# Power.net
KiCad netlist of a schematic drawn in Altium Designer
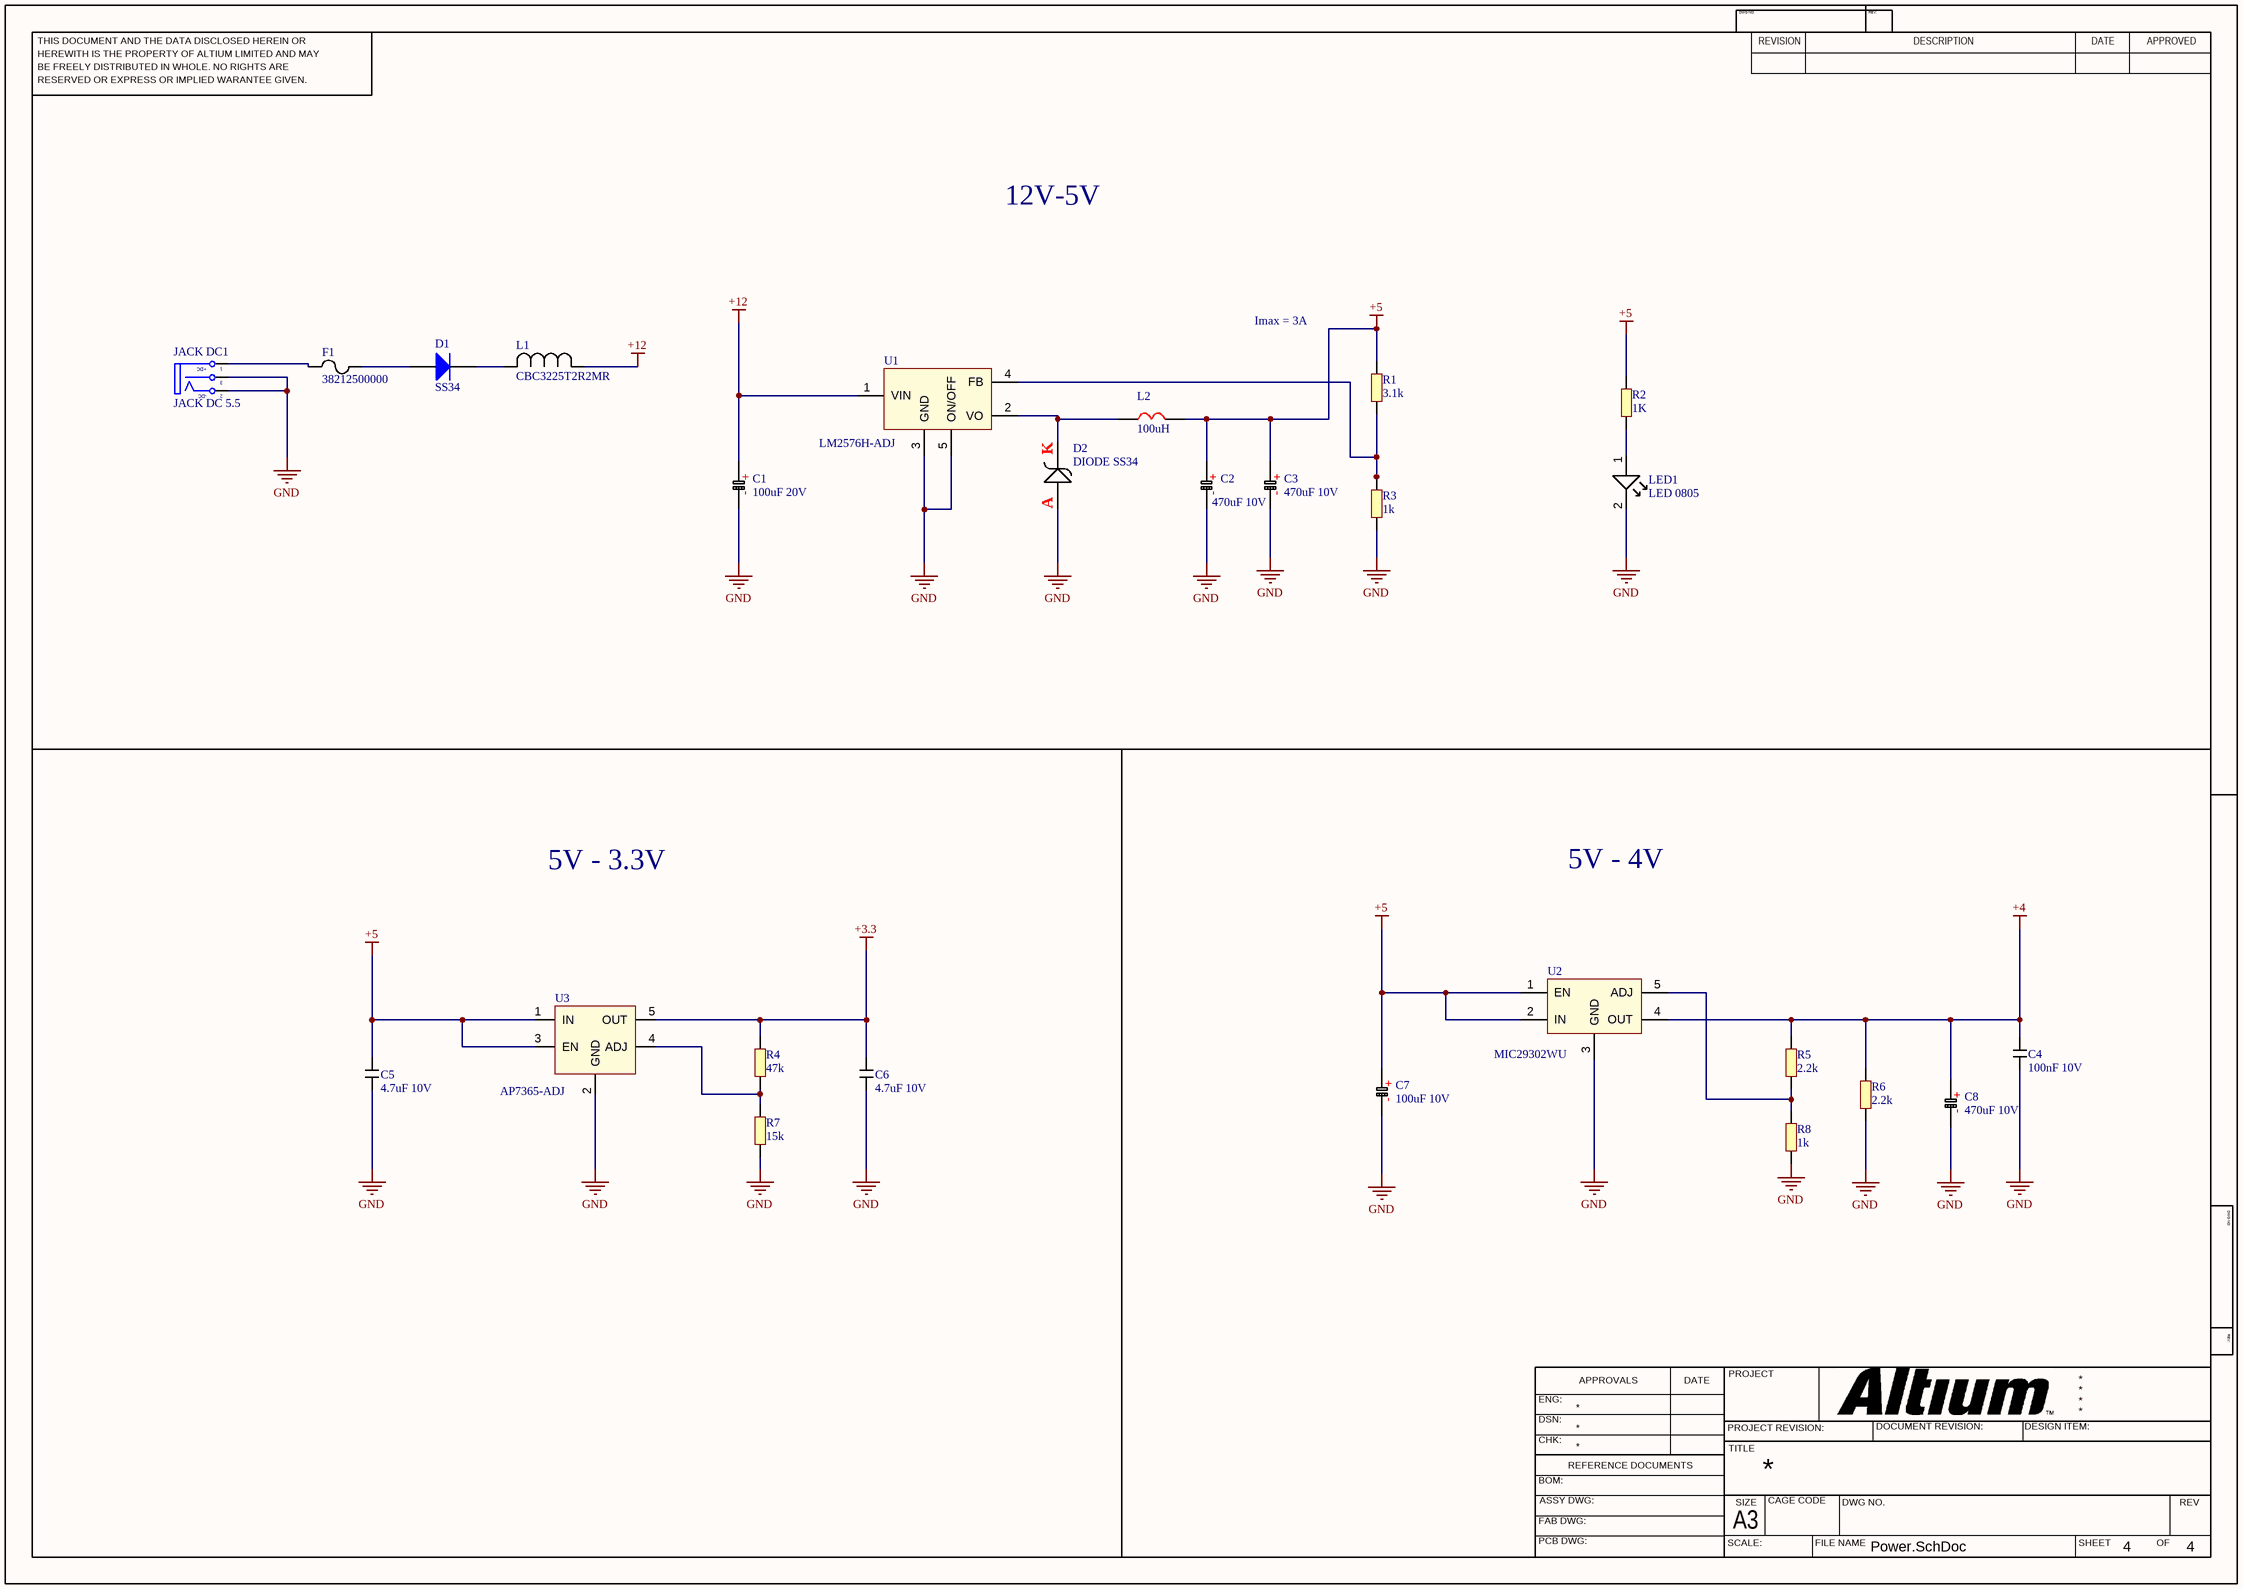
[diagram p0: Power.SchDoc]

(export (version "E")
  (design (tool "Eeschema 10.0.6"))
  (components
    (comp (ref "C1")
      (value "100uF 20V")
      (footprint "CAPACITOR TALTALIUM 7443")
      (libsource (lib "NAVISTAR") (part "C Polarize 8x10.2"))
    )
    (comp (ref "C2")
      (value "470uF 10V")
      (footprint "CAPACITOR TALTALIUM 7443")
      (libsource (lib "NAVISTAR") (part "C Polarize 8x10.2"))
    )
    (comp (ref "C3")
      (value "470uF 10V")
      (footprint "CAPACITOR TALTALIUM 7443")
      (libsource (lib "NAVISTAR") (part "C Polarize 8x10.2"))
    )
    (comp (ref "C4") (value "100nF 10V") (footprint "c 0805") (libsource (lib "NAVISTAR") (part "C 0805")))
    (comp (ref "C5") (value "4.7uF 10V") (footprint "c 0805") (libsource (lib "NAVISTAR") (part "C 0805")))
    (comp (ref "C6") (value "4.7uF 10V") (footprint "c 0805") (libsource (lib "NAVISTAR") (part "C 0805")))
    (comp (ref "C7")
      (value "100uF 10V")
      (footprint "CAPACITOR TALTALIUM 7443")
      (libsource (lib "NAVISTAR") (part "C Polarize 8x10.2"))
    )
    (comp (ref "C8")
      (value "470uF 10V")
      (footprint "CAPACITOR TALTALIUM 7443")
      (libsource (lib "NAVISTAR") (part "C Polarize 8x10.2"))
    )
    (comp (ref "D1")
      (value "SS34")
      (footprint "DIODE SMA")
      (description "Dán")
      (libsource (lib "Altium_Lib_by_KhueNguyenCreator") (part "Diode SS34 ( 1N5822 )"))
    )
    (comp (ref "D2")
      (value "DIODE SS34")
      (footprint "DIODE SS34")
      (libsource (lib "NAVISTAR") (part "DIODE SS34"))
    )
    (comp (ref "F1")
      (value "38212500000")
      (footprint "FUSE_38212500000_LTF")
      (description "No Description Available")
      (fields (field (name "COPYRIGHT") "Copyright (C) 2023 Ultra Librarian. All rights reserved."))
      (libsource (lib "FUSE_38212500000_LTF") (part "38212500000"))
    )
    (comp (ref "JACK DC1")
      (value "JACK DC 5.5")
      (footprint "JACK DC 5.5")
      (libsource (lib "Altium_Lib_by_KhueNguyenCreator") (part "JACK DC 5.5"))
    )
    (comp (ref "L1")
      (value "CBC3225T2R2MR")
      (footprint "IND_TAIYO_CBC3225_TAY")
      (description "No Description Available")
      (fields (field (name "COPYRIGHT") "Copyright (C) 2023 Ultra Librarian. All rights reserved."))
      (libsource (lib "CBC3225T2R2MR") (part "CBC3225T2R2MR"))
    )
    (comp (ref "L2") (value "100uH") (footprint "L 4600") (libsource (lib "NAVISTAR") (part "L 4600")))
    (comp (ref "LED1")
      (value "LED 0805")
      (footprint "LED 0805")
      (libsource (lib "NAVISTAR") (part "LED 0805"))
    )
    (comp (ref "R1") (value "3.1k") (footprint "R 0805") (libsource (lib "NAVISTAR") (part "R 0805")))
    (comp (ref "R2") (value "1K") (footprint "R 0805") (libsource (lib "NAVISTAR") (part "R 0805")))
    (comp (ref "R3") (value "1k") (footprint "R 0805") (libsource (lib "NAVISTAR") (part "R 0805")))
    (comp (ref "R4") (value "47k") (footprint "R 0805") (libsource (lib "NAVISTAR") (part "R 0805")))
    (comp (ref "R5") (value "2.2k") (footprint "R 0805") (libsource (lib "NAVISTAR") (part "R 0805")))
    (comp (ref "R6") (value "2.2k") (footprint "R 0805") (libsource (lib "NAVISTAR") (part "R 0805")))
    (comp (ref "R7") (value "15k") (footprint "R 0805") (libsource (lib "NAVISTAR") (part "R 0805")))
    (comp (ref "R8") (value "1k") (footprint "R 0805") (libsource (lib "NAVISTAR") (part "R 0805")))
    (comp (ref "U1")
      (value "LM2576H-ADJ")
      (footprint "LM2576H")
      (libsource (lib "NAVISTAR") (part "LM2576H"))
    )
    (comp (ref "U2")
      (value "MIC29302WU")
      (footprint "MIC29302WU")
      (libsource (lib "NAVISTAR_SoC") (part "MIC29302WU"))
    )
    (comp (ref "U3")
      (value "AP7365-ADJ")
      (footprint "AP7365-ADJ")
      (libsource (lib "NAVISTAR") (part "AP7365-ADJ"))
    )
  )
  (nets
    (net (code "1") (name "+3.3") (class "Default")
      (node (ref "C6") (pin "2") (pintype "passive"))
      (node (ref "R4") (pin "2") (pintype "passive"))
      (node (ref "U3") (pin "5") (pinfunction "OUT_5") (pintype "passive"))
    )
    (net (code "2") (name "+4") (class "Default")
      (node (ref "C4") (pin "2") (pintype "passive"))
      (node (ref "C8") (pin "1") (pintype "passive"))
      (node (ref "R5") (pin "2") (pintype "passive"))
      (node (ref "R6") (pin "2") (pintype "passive"))
      (node (ref "U2") (pin "4") (pinfunction "OUT_4") (pintype "passive"))
    )
    (net (code "3") (name "+5") (class "Default")
      (node (ref "C2") (pin "1") (pintype "passive"))
      (node (ref "C3") (pin "1") (pintype "passive"))
      (node (ref "C5") (pin "2") (pintype "passive"))
      (node (ref "C7") (pin "1") (pintype "passive"))
      (node (ref "L2") (pin "2") (pintype "passive"))
      (node (ref "R1") (pin "2") (pintype "passive"))
      (node (ref "R2") (pin "2") (pintype "passive"))
      (node (ref "U2") (pin "1") (pinfunction "EN_1") (pintype "passive"))
      (node (ref "U2") (pin "2") (pinfunction "IN_2") (pintype "passive"))
      (node (ref "U3") (pin "1") (pinfunction "IN_1") (pintype "passive"))
      (node (ref "U3") (pin "3") (pinfunction "EN_3") (pintype "passive"))
    )
    (net (code "4") (name "+12") (class "Default")
      (node (ref "C1") (pin "1") (pintype "passive"))
      (node (ref "L1") (pin "1") (pinfunction "1_1") (pintype "passive"))
      (node (ref "U1") (pin "1") (pinfunction "VIN_1") (pintype "passive"))
    )
    (net (code "5") (name "GND") (class "Default")
      (node (ref "C1") (pin "2") (pintype "passive"))
      (node (ref "C2") (pin "2") (pintype "passive"))
      (node (ref "C3") (pin "2") (pintype "passive"))
      (node (ref "C4") (pin "1") (pintype "passive"))
      (node (ref "C5") (pin "1") (pintype "passive"))
      (node (ref "C6") (pin "1") (pintype "passive"))
      (node (ref "C7") (pin "2") (pintype "passive"))
      (node (ref "C8") (pin "2") (pintype "passive"))
      (node (ref "D2") (pin "1") (pintype "passive"))
      (node (ref "JACK DC1") (pin "2") (pinfunction "TN_2") (pintype "passive"))
      (node (ref "JACK DC1") (pin "3") (pinfunction "S_3") (pintype "power_in"))
      (node (ref "LED1") (pin "2") (pintype "passive"))
      (node (ref "R3") (pin "1") (pintype "passive"))
      (node (ref "R6") (pin "1") (pintype "passive"))
      (node (ref "R7") (pin "1") (pintype "passive"))
      (node (ref "R8") (pin "1") (pintype "passive"))
      (node (ref "U1") (pin "3") (pinfunction "GND_3") (pintype "passive"))
      (node (ref "U1") (pin "5") (pinfunction "ON/OFF_5") (pintype "passive"))
      (node (ref "U2") (pin "3") (pinfunction "GND_3") (pintype "passive"))
      (node (ref "U3") (pin "2") (pinfunction "GND_2") (pintype "passive"))
    )
    (net (code "6") (name "Net-(D1-A)") (class "Default")
      (node (ref "D1") (pin "1") (pinfunction "A_1") (pintype "passive"))
      (node (ref "F1") (pin "2") (pinfunction "2_2") (pintype "passive"))
    )
    (net (code "7") (name "Net-(D1-K)") (class "Default")
      (node (ref "D1") (pin "2") (pinfunction "K_2") (pintype "passive"))
      (node (ref "L1") (pin "2") (pinfunction "2_2") (pintype "passive"))
    )
    (net (code "8") (name "Net-(JACK DC1-T)") (class "Default")
      (node (ref "F1") (pin "1") (pinfunction "1_1") (pintype "passive"))
      (node (ref "JACK DC1") (pin "1") (pinfunction "T_1") (pintype "passive"))
    )
    (net (code "9") (name "Net-(LED1-Pad1)") (class "Default")
      (node (ref "LED1") (pin "1") (pintype "passive"))
      (node (ref "R2") (pin "1") (pintype "passive"))
    )
    (net (code "10") (name "Net-(U1-FB)") (class "Default")
      (node (ref "R1") (pin "1") (pintype "passive"))
      (node (ref "R3") (pin "2") (pintype "passive"))
      (node (ref "U1") (pin "4") (pinfunction "FB_4") (pintype "passive"))
    )
    (net (code "11") (name "Net-(U1-VO)") (class "Default")
      (node (ref "D2") (pin "2") (pintype "passive"))
      (node (ref "L2") (pin "1") (pintype "passive"))
      (node (ref "U1") (pin "2") (pinfunction "VO_2") (pintype "passive"))
    )
    (net (code "12") (name "Net-(U2-ADJ)") (class "Default")
      (node (ref "R5") (pin "1") (pintype "passive"))
      (node (ref "R8") (pin "2") (pintype "passive"))
      (node (ref "U2") (pin "5") (pinfunction "ADJ_5") (pintype "passive"))
    )
    (net (code "13") (name "Net-(U3-ADJ)") (class "Default")
      (node (ref "R4") (pin "1") (pintype "passive"))
      (node (ref "R7") (pin "2") (pintype "passive"))
      (node (ref "U3") (pin "4") (pinfunction "ADJ_4") (pintype "passive"))
    )
  )
)
